# Switch.net
KiCad netlist of a schematic drawn in Altium Designer
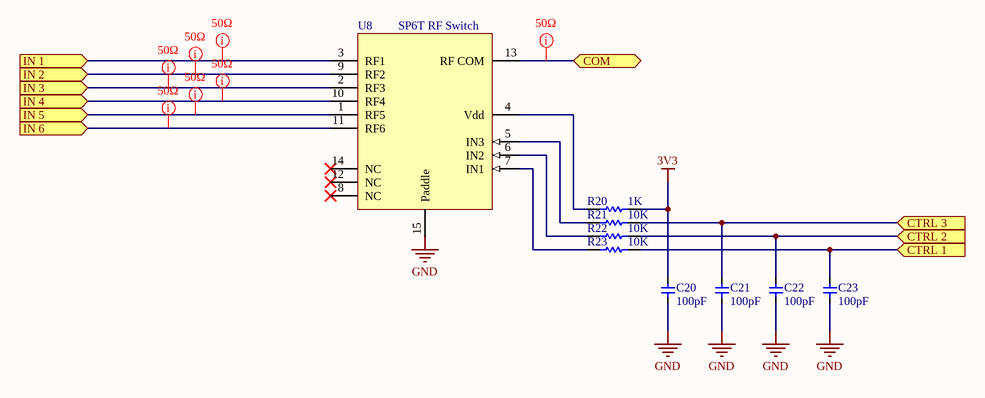
[diagram p0: Switch.SchDoc]

(export (version "E")
  (design (tool "Eeschema 10.0.6"))
  (components
    (comp (ref "C20")
      (value "100pF")
      (footprint "0603C")
      (description "SMT Cap")
      (fields (field (name "PUBLISHER") "Altium Limited"))
      (libsource (lib "Miscellaneous Devices") (part "Cap - SMT Small"))
    )
    (comp (ref "C21")
      (value "100pF")
      (footprint "0603C")
      (description "SMT Cap")
      (fields (field (name "PUBLISHER") "Altium Limited"))
      (libsource (lib "Miscellaneous Devices") (part "Cap - SMT Small"))
    )
    (comp (ref "C22")
      (value "100pF")
      (footprint "0603C")
      (description "SMT Cap")
      (fields (field (name "PUBLISHER") "Altium Limited"))
      (libsource (lib "Miscellaneous Devices") (part "Cap - SMT Small"))
    )
    (comp (ref "C23")
      (value "100pF")
      (footprint "0603C")
      (description "SMT Cap")
      (fields (field (name "PUBLISHER") "Altium Limited"))
      (libsource (lib "Miscellaneous Devices") (part "Cap - SMT Small"))
    )
    (comp (ref "R20")
      (value "1K")
      (footprint "0603R")
      (description "Semiconductor Resistor")
      (fields (field (name "Comment") "RES Semi") (field (name "PUBLISHER") "Altium Limited"))
      (libsource (lib "Miscellaneous Devices") (part "Res Semi"))
    )
    (comp (ref "R21")
      (value "10K")
      (footprint "0603R")
      (description "Semiconductor Resistor")
      (fields (field (name "Comment") "RES Semi") (field (name "PUBLISHER") "Altium Limited"))
      (libsource (lib "Miscellaneous Devices") (part "Res Semi"))
    )
    (comp (ref "R22")
      (value "10K")
      (footprint "0603R")
      (description "Semiconductor Resistor")
      (fields (field (name "Comment") "RES Semi") (field (name "PUBLISHER") "Altium Limited"))
      (libsource (lib "Miscellaneous Devices") (part "Res Semi"))
    )
    (comp (ref "R23")
      (value "10K")
      (footprint "0603R")
      (description "Semiconductor Resistor")
      (fields (field (name "Comment") "RES Semi") (field (name "PUBLISHER") "Altium Limited"))
      (libsource (lib "Miscellaneous Devices") (part "Res Semi"))
    )
    (comp (ref "U8")
      (value "SP6T RF Switch")
      (footprint "MT1817")
      (description "SP6T RF Switch 50Ω 10 to 2700 MHz")
      (libsource (lib "RF Components") (part "JSW6-33DR+"))
    )
  )
  (nets
    (net (code "1") (name "/COM") (class "Default")
      (node (ref "U8") (pin "13") (pinfunction "RF_COM_13") (pintype "passive"))
    )
    (net (code "2") (name "/CTRL 1") (class "Default")
      (node (ref "C23") (pin "2") (pinfunction "2_2") (pintype "passive"))
      (node (ref "R23") (pin "2") (pinfunction "2_2") (pintype "passive"))
    )
    (net (code "3") (name "/CTRL 2") (class "Default")
      (node (ref "C22") (pin "2") (pinfunction "2_2") (pintype "passive"))
      (node (ref "R22") (pin "2") (pinfunction "2_2") (pintype "passive"))
    )
    (net (code "4") (name "/CTRL 3") (class "Default")
      (node (ref "C21") (pin "2") (pinfunction "2_2") (pintype "passive"))
      (node (ref "R21") (pin "2") (pinfunction "2_2") (pintype "passive"))
    )
    (net (code "5") (name "/IN 1") (class "Default")
      (node (ref "U8") (pin "3") (pinfunction "RF1_3") (pintype "passive"))
    )
    (net (code "6") (name "/IN 2") (class "Default")
      (node (ref "U8") (pin "9") (pinfunction "RF2_9") (pintype "passive"))
    )
    (net (code "7") (name "/IN 3") (class "Default")
      (node (ref "U8") (pin "2") (pinfunction "RF3_2") (pintype "passive"))
    )
    (net (code "8") (name "/IN 4") (class "Default")
      (node (ref "U8") (pin "10") (pinfunction "RF4_10") (pintype "passive"))
    )
    (net (code "9") (name "/IN 5") (class "Default")
      (node (ref "U8") (pin "1") (pinfunction "RF5_1") (pintype "passive"))
    )
    (net (code "10") (name "/IN 6") (class "Default")
      (node (ref "U8") (pin "11") (pinfunction "RF6_11") (pintype "passive"))
    )
    (net (code "11") (name "3V3") (class "Default")
      (node (ref "C20") (pin "2") (pinfunction "2_2") (pintype "passive"))
      (node (ref "R20") (pin "2") (pinfunction "2_2") (pintype "passive"))
    )
    (net (code "12") (name "GND") (class "Default")
      (node (ref "C20") (pin "1") (pinfunction "1_1") (pintype "passive"))
      (node (ref "C21") (pin "1") (pinfunction "1_1") (pintype "passive"))
      (node (ref "C22") (pin "1") (pinfunction "1_1") (pintype "passive"))
      (node (ref "C23") (pin "1") (pinfunction "1_1") (pintype "passive"))
      (node (ref "U8") (pin "15") (pinfunction "Paddle_15") (pintype "power_in"))
    )
    (net (code "13") (name "Net-(U8-IN1)") (class "Default")
      (node (ref "R23") (pin "1") (pinfunction "1_1") (pintype "passive"))
      (node (ref "U8") (pin "7") (pinfunction "IN1_7") (pintype "input"))
    )
    (net (code "14") (name "Net-(U8-IN2)") (class "Default")
      (node (ref "R22") (pin "1") (pinfunction "1_1") (pintype "passive"))
      (node (ref "U8") (pin "6") (pinfunction "IN2_6") (pintype "input"))
    )
    (net (code "15") (name "Net-(U8-IN3)") (class "Default")
      (node (ref "R21") (pin "1") (pinfunction "1_1") (pintype "passive"))
      (node (ref "U8") (pin "5") (pinfunction "IN3_5") (pintype "input"))
    )
    (net (code "16") (name "Net-(U8-Vdd)") (class "Default")
      (node (ref "R20") (pin "1") (pinfunction "1_1") (pintype "passive"))
      (node (ref "U8") (pin "4") (pinfunction "Vdd_4") (pintype "power_in"))
    )
    (net (code "17") (name "unconnected-(U8-NC-Pad8)") (class "Default")
      (node (ref "U8") (pin "8") (pinfunction "NC_8") (pintype "passive+no_connect"))
    )
    (net (code "18") (name "unconnected-(U8-NC-Pad12)") (class "Default")
      (node (ref "U8") (pin "12") (pinfunction "NC_12") (pintype "passive+no_connect"))
    )
    (net (code "19") (name "unconnected-(U8-NC-Pad14)") (class "Default")
      (node (ref "U8") (pin "14") (pinfunction "NC_14") (pintype "passive+no_connect"))
    )
  )
)
